# RGB_LED.net
KiCad netlist of a schematic drawn in Altium Designer
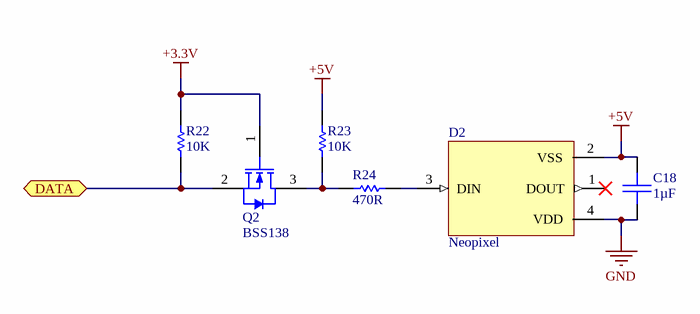
[diagram p0: RGB_LED.SchDoc]

(export (version "E")
  (design (tool "Eeschema 10.0.6"))
  (components
    (comp (ref "C18")
      (value "1µF")
      (footprint "0603_CAP")
      (libsource (lib "Moonlight_Components") (part "Capacitor"))
    )
    (comp (ref "D2")
      (value "Neopixel")
      (footprint "2659")
      (description "Adafruit Neopixel SMD 3535\r\nAdafruit part no. 2659\r\nDigikey part no. 1528-1542-ND")
      (fields (field (name "MP") "2659") (field (name "MF") "Adafruit Industries"))
      (libsource (lib "Moonlight_Components") (part "Neopixel"))
    )
    (comp (ref "Q2")
      (value "BSS138")
      (footprint "INTR-SOT-23-3_V")
      (description "N-Channel HEXFET(R) Power MOSFET, 20 V VDS, +/- 12 V VGS, 4.2 A, 3-Pin SOT23, RoHS, Tape and Reel")
      (fields (field (name "MANUFACTURER") "International Rectifier"))
      (libsource (lib "Moonlight_Components") (part "IRLML2502TRPBF"))
    )
    (comp (ref "R22")
      (value "10K")
      (footprint "0603_RES")
      (libsource (lib "Moonlight_Components") (part "Resistor"))
    )
    (comp (ref "R23")
      (value "10K")
      (footprint "0603_RES")
      (libsource (lib "Moonlight_Components") (part "Resistor"))
    )
    (comp (ref "R24")
      (value "470R")
      (footprint "0603_RES")
      (libsource (lib "Moonlight_Components") (part "Resistor"))
    )
  )
  (nets
    (net (code "1") (name "+3.3V") (class "Default")
      (node (ref "Q2") (pin "1") (pinfunction "G_1") (pintype "passive"))
      (node (ref "R22") (pin "1") (pinfunction "1_1") (pintype "passive"))
    )
    (net (code "2") (name "+5V") (class "Default")
      (node (ref "C18") (pin "1") (pinfunction "1_1") (pintype "passive"))
      (node (ref "D2") (pin "2") (pinfunction "VSS_2") (pintype "power_in"))
      (node (ref "R23") (pin "1") (pinfunction "1_1") (pintype "passive"))
    )
    (net (code "3") (name "/DATA") (class "Default")
      (node (ref "Q2") (pin "2") (pinfunction "S_2") (pintype "passive"))
      (node (ref "R22") (pin "2") (pinfunction "2_2") (pintype "passive"))
    )
    (net (code "4") (name "GND") (class "Default")
      (node (ref "C18") (pin "2") (pinfunction "2_2") (pintype "passive"))
      (node (ref "D2") (pin "4") (pinfunction "VDD_4") (pintype "power_in"))
    )
    (net (code "5") (name "Net-(D2-DIN)") (class "Default")
      (node (ref "D2") (pin "3") (pinfunction "DIN_3") (pintype "input"))
      (node (ref "R24") (pin "2") (pinfunction "2_2") (pintype "passive"))
    )
    (net (code "6") (name "Net-(Q2-D)") (class "Default")
      (node (ref "Q2") (pin "3") (pinfunction "D_3") (pintype "passive"))
      (node (ref "R23") (pin "2") (pinfunction "2_2") (pintype "passive"))
      (node (ref "R24") (pin "1") (pinfunction "1_1") (pintype "passive"))
    )
    (net (code "7") (name "unconnected-(D2-DOUT-Pad1)") (class "Default")
      (node (ref "D2") (pin "1") (pinfunction "DOUT_1") (pintype "output+no_connect"))
    )
  )
)
